# usb.net
KiCad netlist of a schematic drawn in Altium Designer
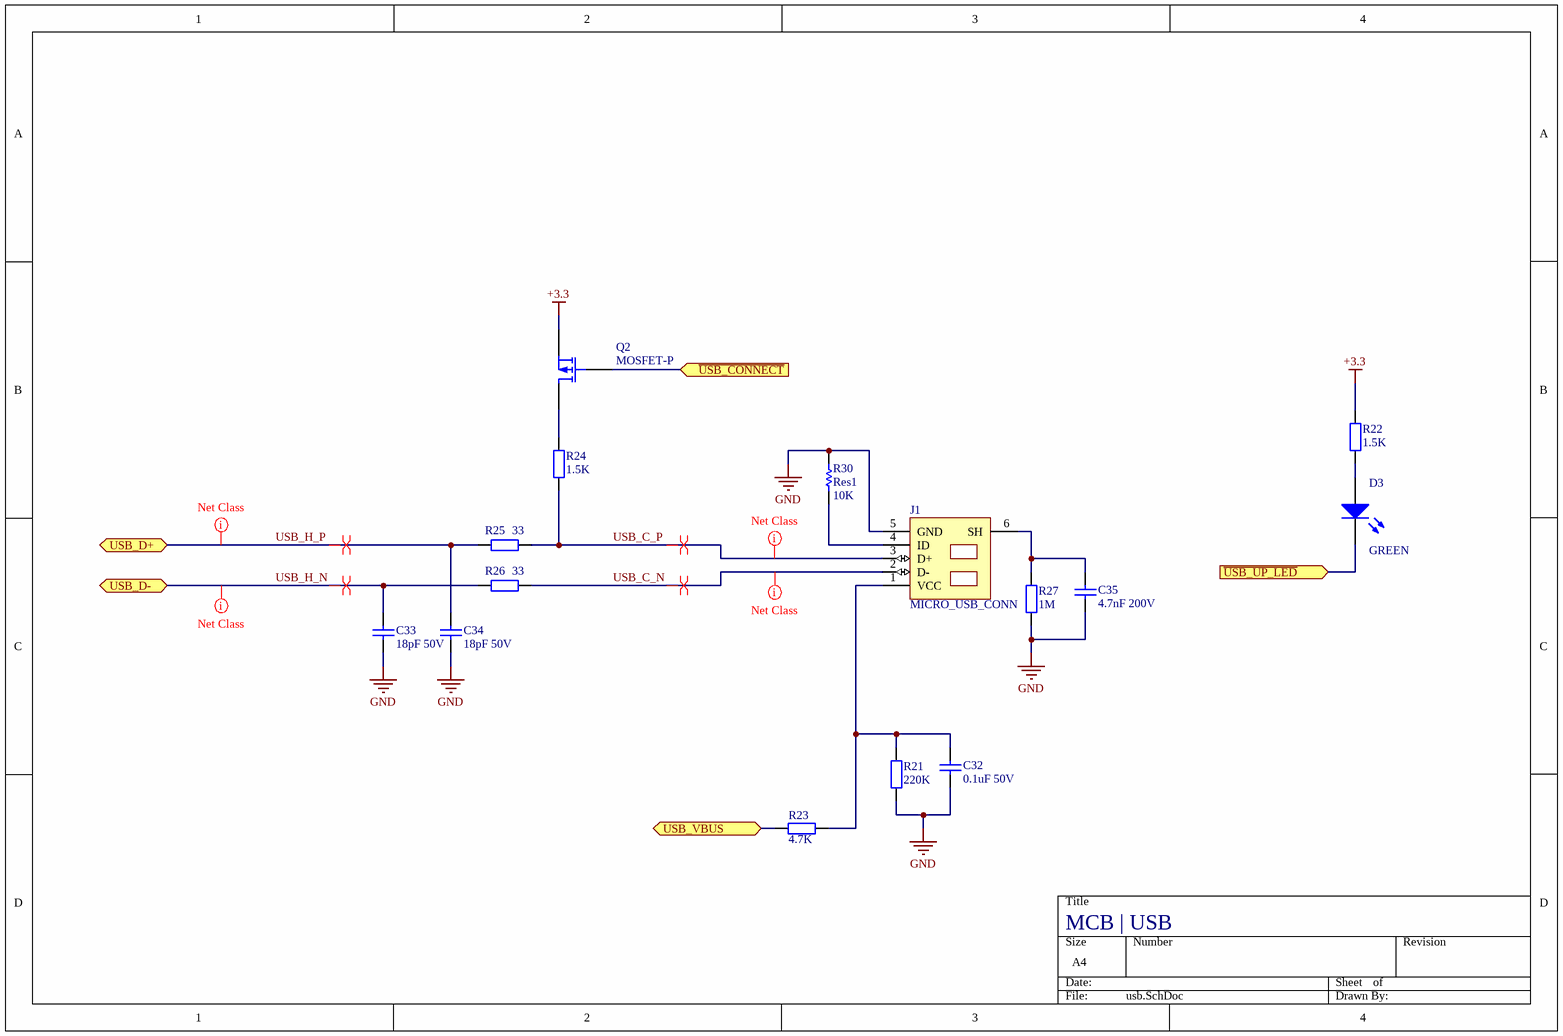
[diagram p0: usb.SchDoc]

(export (version "E")
  (design (tool "Eeschema 10.0.6"))
  (components
    (comp (ref "C32")
      (value "0.1uF 50V")
      (footprint "C0805")
      (description "Capacitor")
      (fields (field (name "Comment") "Cap"))
      (libsource (lib "Miscellaneous Devices") (part "Cap"))
    )
    (comp (ref "C33")
      (value "18pF 50V")
      (footprint "C0805")
      (description "Capacitor")
      (fields (field (name "Comment") "Cap"))
      (libsource (lib "Miscellaneous Devices") (part "Cap"))
    )
    (comp (ref "C34")
      (value "18pF 50V")
      (footprint "C0805")
      (description "Capacitor")
      (fields (field (name "Comment") "Cap"))
      (libsource (lib "Miscellaneous Devices") (part "Cap"))
    )
    (comp (ref "C35")
      (value "4.7nF 200V")
      (footprint "C0805")
      (description "Capacitor")
      (fields (field (name "Comment") "Cap"))
      (libsource (lib "Miscellaneous Devices") (part "Cap"))
    )
    (comp (ref "D3")
      (value "GREEN")
      (footprint "LGQ971")
      (description "Typical RED, GREEN, YELLOW, AMBER GaAs LED")
      (libsource (lib "Miscellaneous Devices") (part "LED2"))
    )
    (comp (ref "J1")
      (value "MICRO_USB_CONN")
      (footprint "USB_MICRO_CONNECTOR")
      (description "MOLEX - 47346-0001 - RECEPTACLE, MICRO USB B, BOTTOM MOUNT")
      (libsource (lib "microUSB") (part "MICRO_USB_CONN"))
    )
    (comp (ref "Q2")
      (value "MOSFET-P")
      (footprint "bsh201")
      (description "P-Channel MOSFET")
      (libsource (lib "Miscellaneous Devices") (part "MOSFET-P"))
    )
    (comp (ref "R21")
      (value "220K")
      (footprint "R0603")
      (description "Resistor")
      (fields (field (name "Comment") "Res"))
      (libsource (lib "Miscellaneous Devices") (part "Res2"))
    )
    (comp (ref "R22")
      (value "1.5K")
      (footprint "R0603")
      (description "Resistor")
      (fields (field (name "Comment") "Res"))
      (libsource (lib "Miscellaneous Devices") (part "Res2"))
    )
    (comp (ref "R23")
      (value "4.7K")
      (footprint "R0603")
      (description "Resistor")
      (fields (field (name "Comment") "Res"))
      (libsource (lib "") (part "Res2_1"))
    )
    (comp (ref "R24")
      (value "1.5K")
      (footprint "R0603")
      (description "Resistor")
      (fields (field (name "Comment") "Res"))
      (libsource (lib "Miscellaneous Devices") (part "Res2"))
    )
    (comp (ref "R25")
      (value "33")
      (footprint "R0603")
      (description "Resistor")
      (fields (field (name "Comment") "Res"))
      (libsource (lib "") (part "Res2_1"))
    )
    (comp (ref "R26")
      (value "33")
      (footprint "R0603")
      (description "Resistor")
      (fields (field (name "Comment") "Res"))
      (libsource (lib "") (part "Res2_1"))
    )
    (comp (ref "R27")
      (value "1M")
      (footprint "R0603")
      (description "Resistor")
      (fields (field (name "Comment") "Res"))
      (libsource (lib "Miscellaneous Devices") (part "Res2"))
    )
    (comp (ref "R30")
      (value "Res1")
      (footprint "R0603")
      (description "Resistor")
      (fields (field (name "ALTIUM_VALUE") "10K") (field (name "PUBLISHER") "Altium Limited"))
      (libsource (lib "Miscellaneous Devices") (part "Res1"))
    )
  )
  (nets
    (net (code "1") (name "+3.3") (class "Default")
      (node (ref "Q2") (pin "3") (pinfunction "S_3") (pintype "passive"))
      (node (ref "R22") (pin "2") (pinfunction "2_2") (pintype "passive"))
    )
    (net (code "2") (name "/USB_C_N") (class "Default")
      (node (ref "J1") (pin "2") (pinfunction "D-_2") (pintype "bidirectional"))
      (node (ref "R26") (pin "2") (pinfunction "2_2") (pintype "passive"))
    )
    (net (code "3") (name "/USB_C_P") (class "Default")
      (node (ref "J1") (pin "3") (pinfunction "D+_3") (pintype "bidirectional"))
      (node (ref "R24") (pin "1") (pinfunction "1_1") (pintype "passive"))
      (node (ref "R25") (pin "2") (pinfunction "2_2") (pintype "passive"))
    )
    (net (code "4") (name "/USB_H_N") (class "Default")
      (node (ref "C33") (pin "1") (pinfunction "1_1") (pintype "passive"))
      (node (ref "R26") (pin "1") (pinfunction "1_1") (pintype "passive"))
    )
    (net (code "5") (name "/USB_H_P") (class "Default")
      (node (ref "C34") (pin "1") (pinfunction "1_1") (pintype "passive"))
      (node (ref "R25") (pin "1") (pinfunction "1_1") (pintype "passive"))
    )
    (net (code "6") (name "/USB_VBUS") (class "Default")
      (node (ref "R23") (pin "1") (pinfunction "1_1") (pintype "passive"))
    )
    (net (code "7") (name "/~{USB_CONNECT}") (class "Default")
      (node (ref "Q2") (pin "2") (pinfunction "G_2") (pintype "passive"))
    )
    (net (code "8") (name "/~{USB_UP_LED}") (class "Default")
      (node (ref "D3") (pin "2") (pinfunction "K_2") (pintype "passive"))
    )
    (net (code "9") (name "GND") (class "Default")
      (node (ref "C32") (pin "2") (pinfunction "2_2") (pintype "passive"))
      (node (ref "C33") (pin "2") (pinfunction "2_2") (pintype "passive"))
      (node (ref "C34") (pin "2") (pinfunction "2_2") (pintype "passive"))
      (node (ref "C35") (pin "2") (pinfunction "2_2") (pintype "passive"))
      (node (ref "J1") (pin "5") (pinfunction "GND_5") (pintype "power_in"))
      (node (ref "R21") (pin "1") (pinfunction "1_1") (pintype "passive"))
      (node (ref "R27") (pin "1") (pinfunction "1_1") (pintype "passive"))
      (node (ref "R30") (pin "2") (pinfunction "2_2") (pintype "passive"))
    )
    (net (code "10") (name "Net-(D3-A)") (class "Default")
      (node (ref "D3") (pin "1") (pinfunction "A_1") (pintype "passive"))
      (node (ref "R22") (pin "1") (pinfunction "1_1") (pintype "passive"))
    )
    (net (code "11") (name "Net-(J1-ID)") (class "Default")
      (node (ref "J1") (pin "4") (pinfunction "ID_4") (pintype "passive"))
      (node (ref "R30") (pin "1") (pinfunction "1_1") (pintype "passive"))
    )
    (net (code "12") (name "Net-(J1-SH)") (class "Default")
      (node (ref "C35") (pin "1") (pinfunction "1_1") (pintype "passive"))
      (node (ref "J1") (pin "6") (pinfunction "SH_6") (pintype "passive"))
      (node (ref "R27") (pin "2") (pinfunction "2_2") (pintype "passive"))
    )
    (net (code "13") (name "Net-(J1-VCC)") (class "Default")
      (node (ref "C32") (pin "1") (pinfunction "1_1") (pintype "passive"))
      (node (ref "J1") (pin "1") (pinfunction "VCC_1") (pintype "power_in"))
      (node (ref "R21") (pin "2") (pinfunction "2_2") (pintype "passive"))
      (node (ref "R23") (pin "2") (pinfunction "2_2") (pintype "passive"))
    )
    (net (code "14") (name "Net-(Q2-D)") (class "Default")
      (node (ref "Q2") (pin "1") (pinfunction "D_1") (pintype "passive"))
      (node (ref "R24") (pin "2") (pinfunction "2_2") (pintype "passive"))
    )
  )
)
